# SMD.net
KiCad netlist of a schematic drawn in EAGLE
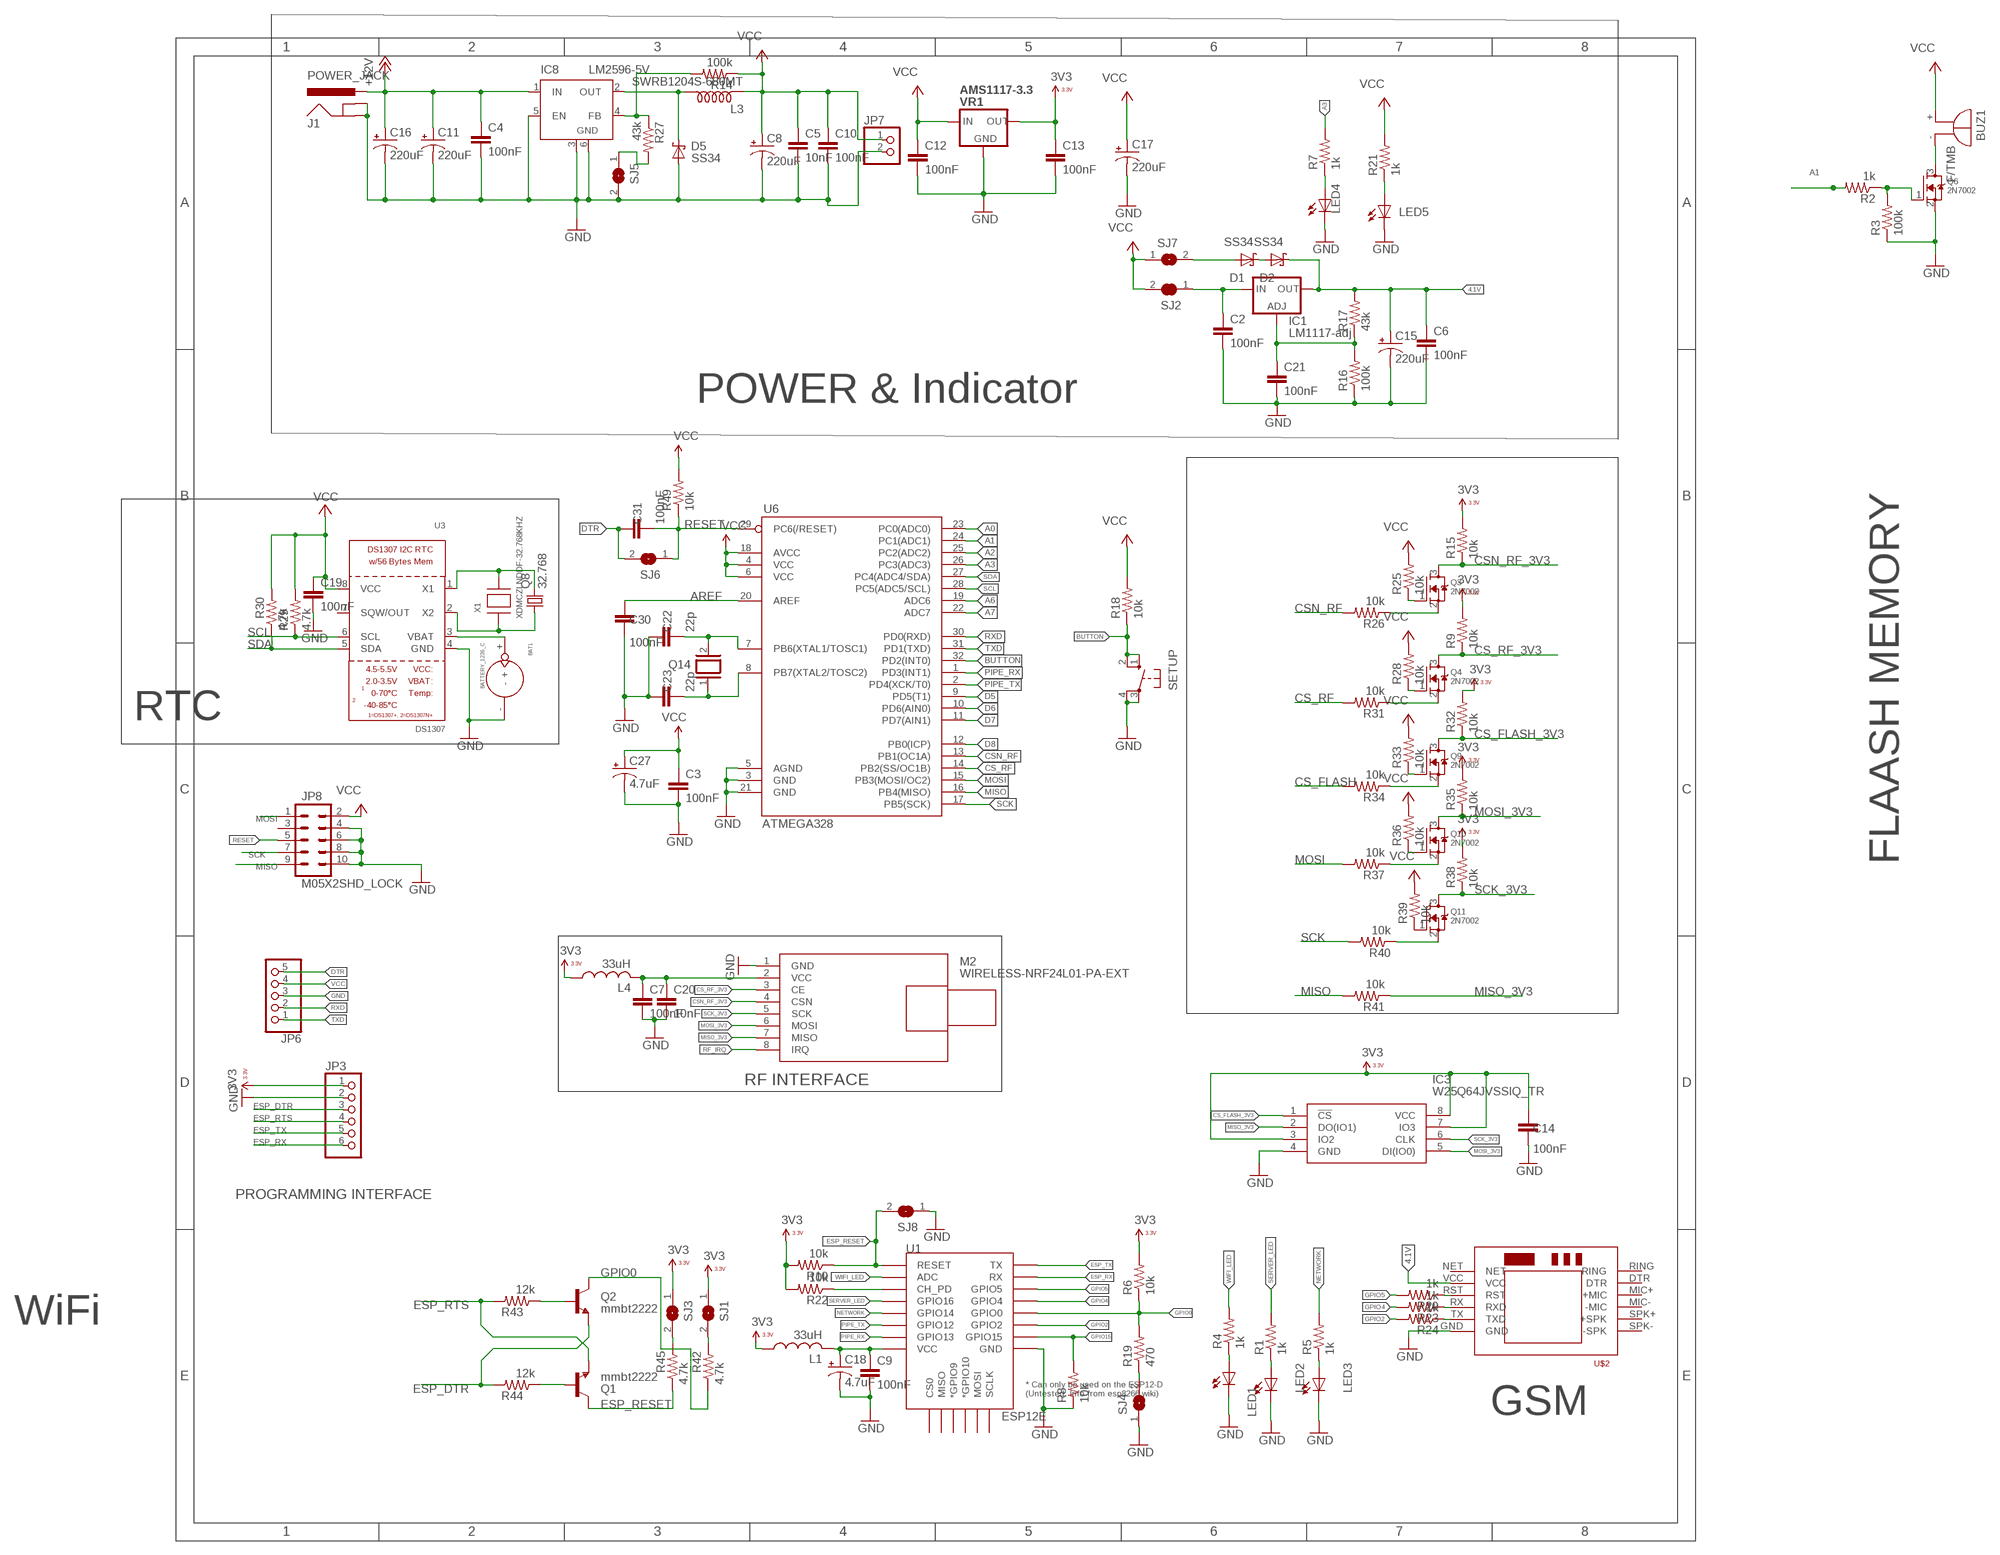
[diagram p0: schematic, sheet 1]

(export (version "E")
  (design (tool "Eeschema 10.0.6"))
  (components
    (comp (ref "BAT1")
      (value "BATTERY_1236_C")
      (footprint "eagle-import:BATTERY_1236_C")
      (libsource (lib "eagle-import") (part "BATTERY_1236_C"))
    )
    (comp (ref "BUZ1")
      (value "F/TMB")
      (footprint "eagle-import:F_TMB")
      (libsource (lib "eagle-import") (part "F/TMB"))
    )
    (comp (ref "C2")
      (value "100nF")
      (footprint "eagle-import:C0805")
      (libsource (lib "eagle-import") (part "C-EUC0805"))
    )
    (comp (ref "C3")
      (value "100nF")
      (footprint "eagle-import:C0805")
      (libsource (lib "eagle-import") (part "C-EUC0805"))
    )
    (comp (ref "C4")
      (value "100nF")
      (footprint "eagle-import:C0805")
      (libsource (lib "eagle-import") (part "C-EUC0805"))
    )
    (comp (ref "C5")
      (value "10nF")
      (footprint "eagle-import:C0805")
      (libsource (lib "eagle-import") (part "C-EUC0805"))
    )
    (comp (ref "C6")
      (value "100nF")
      (footprint "eagle-import:C0805")
      (libsource (lib "eagle-import") (part "C-EUC0805"))
    )
    (comp (ref "C7")
      (value "100nF")
      (footprint "eagle-import:C0805")
      (libsource (lib "eagle-import") (part "C-EUC0805"))
    )
    (comp (ref "C8")
      (value "220uF")
      (footprint "eagle-import:UD-6,3X7,7_NICHICON")
      (libsource (lib "eagle-import") (part "CPOL-USUD-6,3X7,7"))
    )
    (comp (ref "C9")
      (value "100nF")
      (footprint "eagle-import:C0805")
      (libsource (lib "eagle-import") (part "C-EUC0805"))
    )
    (comp (ref "C10")
      (value "100nF")
      (footprint "eagle-import:C0805")
      (libsource (lib "eagle-import") (part "C-EUC0805"))
    )
    (comp (ref "C11")
      (value "220uF")
      (footprint "eagle-import:UD-6,3X7,7_NICHICON")
      (libsource (lib "eagle-import") (part "CPOL-USUD-6,3X7,7"))
    )
    (comp (ref "C12")
      (value "100nF")
      (footprint "eagle-import:C0805")
      (libsource (lib "eagle-import") (part "C-EUC0805"))
    )
    (comp (ref "C13")
      (value "100nF")
      (footprint "eagle-import:C0805")
      (libsource (lib "eagle-import") (part "C-EUC0805"))
    )
    (comp (ref "C14")
      (value "100nF")
      (footprint "eagle-import:C0805")
      (libsource (lib "eagle-import") (part "C-EUC0805"))
    )
    (comp (ref "C15")
      (value "220uF")
      (footprint "eagle-import:UD-6,3X7,7_NICHICON")
      (libsource (lib "eagle-import") (part "CPOL-USUD-6,3X7,7"))
    )
    (comp (ref "C16")
      (value "220uF")
      (footprint "eagle-import:UD-6,3X7,7_NICHICON")
      (libsource (lib "eagle-import") (part "CPOL-USUD-6,3X7,7"))
    )
    (comp (ref "C17")
      (value "220uF")
      (footprint "eagle-import:UD-6,3X7,7_NICHICON")
      (libsource (lib "eagle-import") (part "CPOL-USUD-6,3X7,7"))
    )
    (comp (ref "C18")
      (value "4.7uF")
      (footprint "eagle-import:1206-POLAR")
      (libsource (lib "eagle-import") (part "100UF-POLAR-1206-6.3V-20%(TANT)"))
    )
    (comp (ref "C19")
      (value "100nF")
      (footprint "eagle-import:C0805")
      (libsource (lib "eagle-import") (part "C-EUC0805"))
    )
    (comp (ref "C20")
      (value "10nF")
      (footprint "eagle-import:C0805")
      (libsource (lib "eagle-import") (part "C-EUC0805"))
    )
    (comp (ref "C21")
      (value "100nF")
      (footprint "eagle-import:C0805")
      (libsource (lib "eagle-import") (part "C-EUC0805"))
    )
    (comp (ref "C22")
      (value "22p")
      (footprint "eagle-import:C0805")
      (libsource (lib "eagle-import") (part "C-EUC0805"))
    )
    (comp (ref "C23")
      (value "22p")
      (footprint "eagle-import:C0805")
      (libsource (lib "eagle-import") (part "C-EUC0805"))
    )
    (comp (ref "C27")
      (value "4.7uF")
      (footprint "eagle-import:1206-POLAR")
      (libsource (lib "eagle-import") (part "100UF-POLAR-1206-6.3V-20%(TANT)"))
    )
    (comp (ref "C30")
      (value "100nF")
      (footprint "eagle-import:C0805")
      (libsource (lib "eagle-import") (part "C-EUC0805"))
    )
    (comp (ref "C31")
      (value "100nF")
      (footprint "eagle-import:C0805")
      (libsource (lib "eagle-import") (part "C-EUC0805"))
    )
    (comp (ref "D1")
      (value "SS34")
      (footprint "eagle-import:SMB")
      (libsource (lib "eagle-import") (part "SCHOTTKY-DIODESMD"))
    )
    (comp (ref "D2")
      (value "SS34")
      (footprint "eagle-import:SMB")
      (libsource (lib "eagle-import") (part "SCHOTTKY-DIODESMD"))
    )
    (comp (ref "D5")
      (value "SS34")
      (footprint "eagle-import:SMB")
      (libsource (lib "eagle-import") (part "SCHOTTKY-DIODESMD"))
    )
    (comp (ref "IC1")
      (value "LM1117-adj")
      (footprint "eagle-import:SOT223")
      (libsource (lib "eagle-import") (part "LD117A?S25TR"))
    )
    (comp (ref "IC3")
      (value "W25Q64JVSSIQ_TR")
      (footprint "eagle-import:SOIC127P790X216-8N")
      (fields
        (field (name "MANUFACTURER_PART_NUMBER") "W25Q64JVSSIQ TR")
        (field (name "MOUSER_PART_NUMBER") "454-W25Q64JVSSIQTR")
      )
      (libsource (lib "eagle-import") (part "W25Q64JVSSIQ_TR"))
    )
    (comp (ref "IC8")
      (value "LM2596-5V")
      (footprint "eagle-import:TO263-5")
      (libsource (lib "eagle-import") (part "LM2596S"))
    )
    (comp (ref "J1")
      (value "POWER_JACK")
      (footprint "eagle-import:POWER_JACK_PTH")
      (libsource (lib "eagle-import") (part "POWER_JACK"))
    )
    (comp (ref "JP3")
      (value "PINHD-1X6")
      (footprint "eagle-import:1X06")
      (libsource (lib "eagle-import") (part "PINHD-1X6"))
    )
    (comp (ref "JP6")
      (value "PINHD-1X5")
      (footprint "eagle-import:1X05")
      (libsource (lib "eagle-import") (part "PINHD-1X5"))
    )
    (comp (ref "JP7")
      (value "PINHD-1X2")
      (footprint "eagle-import:1X02")
      (libsource (lib "eagle-import") (part "PINHD-1X2"))
    )
    (comp (ref "JP8")
      (value "M05X2SHD_LOCK")
      (footprint "eagle-import:2X5-SHROUDED_LOCK")
      (libsource (lib "eagle-import") (part "M05X2SHD_LOCK"))
    )
    (comp (ref "L1")
      (value "33uH")
      (footprint "eagle-import:L0805")
      (libsource (lib "eagle-import") (part "L-USL0805"))
    )
    (comp (ref "L3")
      (value "SWRB1204S-680MT")
      (footprint "eagle-import:D10F")
      (libsource (lib "eagle-import") (part "A814AY-330M"))
    )
    (comp (ref "L4")
      (value "33uH")
      (footprint "eagle-import:L0805")
      (libsource (lib "eagle-import") (part "L-USL0805"))
    )
    (comp (ref "LED1")
      (value "LED3MM")
      (footprint "eagle-import:LED3MM")
      (libsource (lib "eagle-import") (part "LED3MM"))
    )
    (comp (ref "LED2")
      (value "LED3MM")
      (footprint "eagle-import:LED3MM")
      (libsource (lib "eagle-import") (part "LED3MM"))
    )
    (comp (ref "LED3")
      (value "LED3MM")
      (footprint "eagle-import:LED3MM")
      (libsource (lib "eagle-import") (part "LED3MM"))
    )
    (comp (ref "LED4")
      (value "LED3MM")
      (footprint "eagle-import:LED3MM")
      (libsource (lib "eagle-import") (part "LED3MM"))
    )
    (comp (ref "LED5")
      (value "LED3MM")
      (footprint "eagle-import:LED3MM")
      (libsource (lib "eagle-import") (part "LED3MM"))
    )
    (comp (ref "M2")
      (value "WIRELESS-NRF24L01-PA-EXT")
      (footprint "eagle-import:WIRELESS-NRF24L01-PA-EXT")
      (libsource (lib "eagle-import") (part "WIRELESS-NRF24L01-PA-EXT"))
    )
    (comp (ref "Q1")
      (value "mmbt2222")
      (footprint "eagle-import:SOT23-3")
      (libsource (lib "eagle-import") (part "TRANSISTOR_NPNSOT23-3"))
    )
    (comp (ref "Q2")
      (value "mmbt2222")
      (footprint "eagle-import:SOT23-3")
      (libsource (lib "eagle-import") (part "TRANSISTOR_NPNSOT23-3"))
    )
    (comp (ref "Q3")
      (value "2N7002")
      (footprint "eagle-import:SOT23")
      (libsource (lib "eagle-import") (part "MOSFET-NREFLOW"))
    )
    (comp (ref "Q4")
      (value "2N7002")
      (footprint "eagle-import:SOT23")
      (libsource (lib "eagle-import") (part "MOSFET-NREFLOW"))
    )
    (comp (ref "Q6")
      (value "2N7002")
      (footprint "eagle-import:SOT23")
      (libsource (lib "eagle-import") (part "MOSFET-NREFLOW"))
    )
    (comp (ref "Q8")
      (value "32.768")
      (footprint "eagle-import:TC26H")
      (libsource (lib "eagle-import") (part "CRYTALTC26H"))
    )
    (comp (ref "Q9")
      (value "2N7002")
      (footprint "eagle-import:SOT23")
      (libsource (lib "eagle-import") (part "MOSFET-NREFLOW"))
    )
    (comp (ref "Q10")
      (value "2N7002")
      (footprint "eagle-import:SOT23")
      (libsource (lib "eagle-import") (part "MOSFET-NREFLOW"))
    )
    (comp (ref "Q11")
      (value "2N7002")
      (footprint "eagle-import:SOT23")
      (libsource (lib "eagle-import") (part "MOSFET-NREFLOW"))
    )
    (comp (ref "Q14")
      (value "XTAL/S")
      (footprint "eagle-import:QS")
      (libsource (lib "eagle-import") (part "XTAL/S"))
    )
    (comp (ref "R1")
      (value "1k")
      (footprint "eagle-import:R0805")
      (libsource (lib "eagle-import") (part "resistor_R-US_R0805"))
    )
    (comp (ref "R2")
      (value "1k")
      (footprint "eagle-import:R0805")
      (libsource (lib "eagle-import") (part "resistor_R-US_R0805"))
    )
    (comp (ref "R3")
      (value "100k")
      (footprint "eagle-import:R0805")
      (libsource (lib "eagle-import") (part "resistor_R-US_R0805"))
    )
    (comp (ref "R4")
      (value "1k")
      (footprint "eagle-import:R0805")
      (libsource (lib "eagle-import") (part "resistor_R-US_R0805"))
    )
    (comp (ref "R5")
      (value "1k")
      (footprint "eagle-import:R0805")
      (libsource (lib "eagle-import") (part "resistor_R-US_R0805"))
    )
    (comp (ref "R6")
      (value "10k")
      (footprint "eagle-import:R0805")
      (libsource (lib "eagle-import") (part "resistor_R-US_R0805"))
    )
    (comp (ref "R7")
      (value "1k")
      (footprint "eagle-import:R0805")
      (libsource (lib "eagle-import") (part "resistor_R-US_R0805"))
    )
    (comp (ref "R8")
      (value "10k")
      (footprint "eagle-import:R0805")
      (libsource (lib "eagle-import") (part "resistor_R-US_R0805"))
    )
    (comp (ref "R9")
      (value "10k")
      (footprint "eagle-import:R0805")
      (libsource (lib "eagle-import") (part "resistor_R-US_R0805"))
    )
    (comp (ref "R10")
      (value "10k")
      (footprint "eagle-import:R0805")
      (libsource (lib "eagle-import") (part "resistor_R-US_R0805"))
    )
    (comp (ref "R14")
      (value "100k")
      (footprint "eagle-import:R0805")
      (libsource (lib "eagle-import") (part "resistor_R-US_R0805"))
    )
    (comp (ref "R15")
      (value "10k")
      (footprint "eagle-import:R0805")
      (libsource (lib "eagle-import") (part "resistor_R-US_R0805"))
    )
    (comp (ref "R16")
      (value "100k")
      (footprint "eagle-import:R0805")
      (libsource (lib "eagle-import") (part "resistor_R-US_R0805"))
    )
    (comp (ref "R17")
      (value "43k")
      (footprint "eagle-import:R0805")
      (libsource (lib "eagle-import") (part "resistor_R-US_R0805"))
    )
    (comp (ref "R18")
      (value "10k")
      (footprint "eagle-import:R0805")
      (libsource (lib "eagle-import") (part "resistor_R-US_R0805"))
    )
    (comp (ref "R19")
      (value "470")
      (footprint "eagle-import:R0805")
      (libsource (lib "eagle-import") (part "resistor_R-US_R0805"))
    )
    (comp (ref "R20")
      (value "1k")
      (footprint "eagle-import:R0805")
      (libsource (lib "eagle-import") (part "resistor_R-US_R0805"))
    )
    (comp (ref "R21")
      (value "1k")
      (footprint "eagle-import:R0805")
      (libsource (lib "eagle-import") (part "resistor_R-US_R0805"))
    )
    (comp (ref "R22")
      (value "10k")
      (footprint "eagle-import:R0805")
      (libsource (lib "eagle-import") (part "resistor_R-US_R0805"))
    )
    (comp (ref "R23")
      (value "1k")
      (footprint "eagle-import:R0805")
      (libsource (lib "eagle-import") (part "resistor_R-US_R0805"))
    )
    (comp (ref "R24")
      (value "1k")
      (footprint "eagle-import:R0805")
      (libsource (lib "eagle-import") (part "resistor_R-US_R0805"))
    )
    (comp (ref "R25")
      (value "10k")
      (footprint "eagle-import:R0805")
      (libsource (lib "eagle-import") (part "resistor_R-US_R0805"))
    )
    (comp (ref "R26")
      (value "10k")
      (footprint "eagle-import:R0805")
      (libsource (lib "eagle-import") (part "resistor_R-US_R0805"))
    )
    (comp (ref "R27")
      (value "43k")
      (footprint "eagle-import:R0805")
      (libsource (lib "eagle-import") (part "resistor_R-US_R0805"))
    )
    (comp (ref "R28")
      (value "10k")
      (footprint "eagle-import:R0805")
      (libsource (lib "eagle-import") (part "resistor_R-US_R0805"))
    )
    (comp (ref "R29")
      (value "4.7k")
      (footprint "eagle-import:R0805")
      (libsource (lib "eagle-import") (part "resistor_R-US_R0805"))
    )
    (comp (ref "R30")
      (value "4.7k")
      (footprint "eagle-import:R0805")
      (libsource (lib "eagle-import") (part "resistor_R-US_R0805"))
    )
    (comp (ref "R31")
      (value "10k")
      (footprint "eagle-import:R0805")
      (libsource (lib "eagle-import") (part "resistor_R-US_R0805"))
    )
    (comp (ref "R32")
      (value "10k")
      (footprint "eagle-import:R0805")
      (libsource (lib "eagle-import") (part "resistor_R-US_R0805"))
    )
    (comp (ref "R33")
      (value "10k")
      (footprint "eagle-import:R0805")
      (libsource (lib "eagle-import") (part "resistor_R-US_R0805"))
    )
    (comp (ref "R34")
      (value "10k")
      (footprint "eagle-import:R0805")
      (libsource (lib "eagle-import") (part "resistor_R-US_R0805"))
    )
    (comp (ref "R35")
      (value "10k")
      (footprint "eagle-import:R0805")
      (libsource (lib "eagle-import") (part "resistor_R-US_R0805"))
    )
    (comp (ref "R36")
      (value "10k")
      (footprint "eagle-import:R0805")
      (libsource (lib "eagle-import") (part "resistor_R-US_R0805"))
    )
    (comp (ref "R37")
      (value "10k")
      (footprint "eagle-import:R0805")
      (libsource (lib "eagle-import") (part "resistor_R-US_R0805"))
    )
    (comp (ref "R38")
      (value "10k")
      (footprint "eagle-import:R0805")
      (libsource (lib "eagle-import") (part "resistor_R-US_R0805"))
    )
    (comp (ref "R39")
      (value "10k")
      (footprint "eagle-import:R0805")
      (libsource (lib "eagle-import") (part "resistor_R-US_R0805"))
    )
    (comp (ref "R40")
      (value "10k")
      (footprint "eagle-import:R0805")
      (libsource (lib "eagle-import") (part "resistor_R-US_R0805"))
    )
    (comp (ref "R41")
      (value "10k")
      (footprint "eagle-import:R0805")
      (libsource (lib "eagle-import") (part "resistor_R-US_R0805"))
    )
    (comp (ref "R42")
      (value "4.7k")
      (footprint "eagle-import:R0805")
      (libsource (lib "eagle-import") (part "resistor_R-US_R0805"))
    )
    (comp (ref "R43")
      (value "12k")
      (footprint "eagle-import:R0805")
      (libsource (lib "eagle-import") (part "resistor_R-US_R0805"))
    )
    (comp (ref "R44")
      (value "12k")
      (footprint "eagle-import:R0805")
      (libsource (lib "eagle-import") (part "resistor_R-US_R0805"))
    )
    (comp (ref "R45")
      (value "4.7k")
      (footprint "eagle-import:R0805")
      (libsource (lib "eagle-import") (part "resistor_R-US_R0805"))
    )
    (comp (ref "R49")
      (value "10k")
      (footprint "eagle-import:R0805")
      (libsource (lib "eagle-import") (part "R-US_R0805"))
    )
    (comp (ref "SETUP")
      (value "10-XX")
      (footprint "eagle-import:B3F-10XX")
      (fields (field (name "MPN") "B3F-1000"))
      (libsource (lib "eagle-import") (part "10-XX"))
    )
    (comp (ref "SJ1") (value "SJ") (footprint "eagle-import:SJ") (libsource (lib "eagle-import") (part "SJ")))
    (comp (ref "SJ2")
      (value "SOLDERJUMPER_CLOSED")
      (footprint "eagle-import:SOLDERJUMPER_CLOSEDWIRE")
      (libsource (lib "eagle-import") (part "SOLDERJUMPER_CLOSED"))
    )
    (comp (ref "SJ3") (value "SJ") (footprint "eagle-import:SJ") (libsource (lib "eagle-import") (part "SJ")))
    (comp (ref "SJ4") (value "SJ") (footprint "eagle-import:SJ") (libsource (lib "eagle-import") (part "SJ")))
    (comp (ref "SJ5") (value "SJ") (footprint "eagle-import:SJ") (libsource (lib "eagle-import") (part "SJ")))
    (comp (ref "SJ6") (value "SJ") (footprint "eagle-import:SJ") (libsource (lib "eagle-import") (part "SJ")))
    (comp (ref "SJ7") (value "SJ") (footprint "eagle-import:SJ") (libsource (lib "eagle-import") (part "SJ")))
    (comp (ref "SJ8") (value "SJ") (footprint "eagle-import:SJ") (libsource (lib "eagle-import") (part "SJ")))
    (comp (ref "U$2")
      (value "SIM800LMODULE")
      (footprint "eagle-import:SIM800LMODULE")
      (libsource (lib "eagle-import") (part "SIM800LMODULE"))
    )
    (comp (ref "U1")
      (value "ESP12E")
      (footprint "eagle-import:ESP12E-SMD")
      (libsource (lib "eagle-import") (part "ESP12ESMD"))
    )
    (comp (ref "U3")
      (value "DS1307")
      (footprint "eagle-import:SOIC8_150MIL")
      (libsource (lib "eagle-import") (part "RTC_DS1307"))
    )
    (comp (ref "U6")
      (value "ATMEGA328")
      (footprint "eagle-import:TQFP32-08")
      (libsource (lib "eagle-import") (part "ATMEGA168"))
    )
    (comp (ref "VR1")
      (value "AMS1117-3.3")
      (footprint "eagle-import:SOT223")
      (libsource (lib "eagle-import") (part "NCP1117ST50T3G"))
    )
    (comp (ref "X1")
      (value "XDMCZLNDDF-32.768KHZ")
      (footprint "eagle-import:XTAL3215")
      (libsource (lib "eagle-import") (part "XTAL-3.2X1.5"))
    )
  )
  (nets
    (net (code "1") (name "+12V") (class "Default")
      (node (ref "C11") (pin "+") (pinfunction "+_+") (pintype "passive"))
      (node (ref "C16") (pin "+") (pinfunction "+_+") (pintype "passive"))
      (node (ref "C4") (pin "1") (pinfunction "1_1") (pintype "passive"))
      (node (ref "IC8") (pin "1") (pinfunction "IN_1") (pintype "input"))
      (node (ref "J1") (pin "PWR") (pinfunction "PWR_PWR") (pintype "bidirectional"))
    )
    (net (code "2") (name "/AREF") (class "Default")
      (node (ref "C30") (pin "2") (pinfunction "2_2") (pintype "passive"))
      (node (ref "U6") (pin "20") (pinfunction "AREF_20") (pintype "bidirectional"))
    )
    (net (code "3") (name "/CS_FLASH") (class "Default")
      (node (ref "R34") (pin "2") (pinfunction "2_2") (pintype "passive"))
    )
    (net (code "4") (name "/ESP_DTR") (class "Default")
      (node (ref "JP3") (pin "3") (pinfunction "3_3") (pintype "passive"))
      (node (ref "Q2") (pin "2") (pinfunction "E_2") (pintype "passive"))
      (node (ref "R44") (pin "2") (pinfunction "2_2") (pintype "passive"))
    )
    (net (code "5") (name "/ESP_RTS") (class "Default")
      (node (ref "JP3") (pin "4") (pinfunction "4_4") (pintype "passive"))
      (node (ref "Q1") (pin "2") (pinfunction "E_2") (pintype "passive"))
      (node (ref "R43") (pin "2") (pinfunction "2_2") (pintype "passive"))
    )
    (net (code "6") (name "3V3") (class "Default")
      (node (ref "C13") (pin "1") (pinfunction "1_1") (pintype "passive"))
      (node (ref "C14") (pin "2") (pinfunction "2_2") (pintype "passive"))
      (node (ref "IC3") (pin "3") (pinfunction "IO2_3") (pintype "bidirectional"))
      (node (ref "IC3") (pin "7") (pinfunction "IO3_7") (pintype "bidirectional"))
      (node (ref "IC3") (pin "8") (pinfunction "VCC_8") (pintype "bidirectional"))
      (node (ref "JP3") (pin "1") (pinfunction "1_1") (pintype "passive"))
      (node (ref "L1") (pin "1") (pinfunction "1_1") (pintype "passive"))
      (node (ref "L4") (pin "1") (pinfunction "1_1") (pintype "passive"))
      (node (ref "R10") (pin "2") (pinfunction "2_2") (pintype "passive"))
      (node (ref "R15") (pin "2") (pinfunction "2_2") (pintype "passive"))
      (node (ref "R22") (pin "2") (pinfunction "2_2") (pintype "passive"))
      (node (ref "R32") (pin "2") (pinfunction "2_2") (pintype "passive"))
      (node (ref "R35") (pin "2") (pinfunction "2_2") (pintype "passive"))
      (node (ref "R38") (pin "2") (pinfunction "2_2") (pintype "passive"))
      (node (ref "R6") (pin "2") (pinfunction "2_2") (pintype "passive"))
      (node (ref "R9") (pin "2") (pinfunction "2_2") (pintype "passive"))
      (node (ref "SJ1") (pin "1") (pinfunction "1_1") (pintype "passive"))
      (node (ref "SJ3") (pin "1") (pinfunction "1_1") (pintype "passive"))
      (node (ref "VR1") (pin "2") (pinfunction "OUT_2") (pintype "output"))
      (node (ref "VR1") (pin "4") (pinfunction "OUT_4") (pintype "output"))
    )
    (net (code "7") (name "4.1V") (class "Default")
      (node (ref "C15") (pin "+") (pinfunction "+_+") (pintype "passive"))
      (node (ref "C6") (pin "1") (pinfunction "1_1") (pintype "passive"))
      (node (ref "D2") (pin "C") (pinfunction "C_C") (pintype "passive"))
      (node (ref "IC1") (pin "4") (pinfunction "OUT_4") (pintype "passive"))
      (node (ref "R17") (pin "2") (pinfunction "2_2") (pintype "passive"))
      (node (ref "U$2") (pin "VCC") (pinfunction "VCC_VCC") (pintype "bidirectional"))
    )
    (net (code "8") (name "A0") (class "Default")
      (node (ref "U6") (pin "23") (pinfunction "PC0(ADC0)_23") (pintype "bidirectional"))
    )
    (net (code "9") (name "A1") (class "Default")
      (node (ref "R2") (pin "2") (pinfunction "2_2") (pintype "passive"))
      (node (ref "U6") (pin "24") (pinfunction "PC1(ADC1)_24") (pintype "bidirectional"))
    )
    (net (code "10") (name "A2") (class "Default")
      (node (ref "U6") (pin "25") (pinfunction "PC2(ADC2)_25") (pintype "bidirectional"))
    )
    (net (code "11") (name "A3") (class "Default")
      (node (ref "R7") (pin "2") (pinfunction "2_2") (pintype "passive"))
      (node (ref "U6") (pin "26") (pinfunction "PC3(ADC3)_26") (pintype "bidirectional"))
    )
    (net (code "12") (name "A6") (class "Default")
      (node (ref "U6") (pin "19") (pinfunction "ADC6_19") (pintype "bidirectional"))
    )
    (net (code "13") (name "A7") (class "Default")
      (node (ref "U6") (pin "22") (pinfunction "ADC7_22") (pintype "bidirectional"))
    )
    (net (code "14") (name "BUTTON") (class "Default")
      (node (ref "R18") (pin "1") (pinfunction "1_1") (pintype "passive"))
      (node (ref "SETUP") (pin "1") (pinfunction "S_1") (pintype "passive"))
      (node (ref "SETUP") (pin "2") (pinfunction "S1_2") (pintype "passive"))
      (node (ref "U6") (pin "32") (pinfunction "PD2(INT0)_32") (pintype "bidirectional"))
    )
    (net (code "15") (name "CSN_RF") (class "Default")
      (node (ref "R26") (pin "2") (pinfunction "2_2") (pintype "passive"))
      (node (ref "U6") (pin "13") (pinfunction "PB1(OC1A)_13") (pintype "bidirectional"))
    )
    (net (code "16") (name "CSN_RF_3V3") (class "Default")
      (node (ref "M2") (pin "4") (pinfunction "CSN_4") (pintype "bidirectional"))
      (node (ref "Q3") (pin "3") (pinfunction "D_3") (pintype "bidirectional"))
      (node (ref "R15") (pin "1") (pinfunction "1_1") (pintype "passive"))
    )
    (net (code "17") (name "CS_FLASH_3V3") (class "Default")
      (node (ref "IC3") (pin "1") (pinfunction "~{CS}_1") (pintype "bidirectional"))
      (node (ref "Q9") (pin "3") (pinfunction "D_3") (pintype "bidirectional"))
      (node (ref "R32") (pin "1") (pinfunction "1_1") (pintype "passive"))
    )
    (net (code "18") (name "CS_RF") (class "Default")
      (node (ref "R31") (pin "2") (pinfunction "2_2") (pintype "passive"))
      (node (ref "U6") (pin "14") (pinfunction "PB2(SS/OC1B)_14") (pintype "bidirectional"))
    )
    (net (code "19") (name "CS_RF_3V3") (class "Default")
      (node (ref "M2") (pin "3") (pinfunction "CE_3") (pintype "bidirectional"))
      (node (ref "Q4") (pin "3") (pinfunction "D_3") (pintype "bidirectional"))
      (node (ref "R9") (pin "1") (pinfunction "1_1") (pintype "passive"))
    )
    (net (code "20") (name "D5") (class "Default")
      (node (ref "U6") (pin "9") (pinfunction "PD5(T1)_9") (pintype "bidirectional"))
    )
    (net (code "21") (name "D6") (class "Default")
      (node (ref "U6") (pin "10") (pinfunction "PD6(AIN0)_10") (pintype "bidirectional"))
    )
    (net (code "22") (name "D7") (class "Default")
      (node (ref "U6") (pin "11") (pinfunction "PD7(AIN1)_11") (pintype "bidirectional"))
    )
    (net (code "23") (name "D8") (class "Default")
      (node (ref "U6") (pin "12") (pinfunction "PB0(ICP)_12") (pintype "bidirectional"))
    )
    (net (code "24") (name "DTR") (class "Default")
      (node (ref "C31") (pin "2") (pinfunction "2_2") (pintype "passive"))
      (node (ref "JP6") (pin "5") (pinfunction "5_5") (pintype "passive"))
      (node (ref "SJ6") (pin "2") (pinfunction "2_2") (pintype "passive"))
    )
    (net (code "25") (name "ESP_RESET") (class "Default")
      (node (ref "Q1") (pin "3") (pinfunction "C_3") (pintype "passive"))
      (node (ref "R10") (pin "1") (pinfunction "1_1") (pintype "passive"))
      (node (ref "R45") (pin "1") (pinfunction "1_1") (pintype "passive"))
      (node (ref "SJ8") (pin "2") (pinfunction "2_2") (pintype "passive"))
      (node (ref "U1") (pin "RESET") (pinfunction "RESET_RESET") (pintype "bidirectional"))
    )
    (net (code "26") (name "ESP_RX") (class "Default")
      (node (ref "JP3") (pin "6") (pinfunction "6_6") (pintype "passive"))
      (node (ref "U1") (pin "RXD0") (pinfunction "RX_RXD0") (pintype "bidirectional"))
    )
    (net (code "27") (name "ESP_TX") (class "Default")
      (node (ref "JP3") (pin "5") (pinfunction "5_5") (pintype "passive"))
      (node (ref "U1") (pin "TXD0") (pinfunction "TX_TXD0") (pintype "bidirectional"))
    )
    (net (code "28") (name "GND") (class "Default")
      (node (ref "BAT1") (pin "-") (pinfunction "-_-") (pintype "bidirectional"))
      (node (ref "C10") (pin "2") (pinfunction "2_2") (pintype "passive"))
      (node (ref "C11") (pin "-") (pinfunction "-_-") (pintype "passive"))
      (node (ref "C12") (pin "2") (pinfunction "2_2") (pintype "passive"))
      (node (ref "C13") (pin "2") (pinfunction "2_2") (pintype "passive"))
      (node (ref "C14") (pin "1") (pinfunction "1_1") (pintype "passive"))
      (node (ref "C15") (pin "-") (pinfunction "-_-") (pintype "passive"))
      (node (ref "C16") (pin "-") (pinfunction "-_-") (pintype "passive"))
      (node (ref "C17") (pin "-") (pinfunction "-_-") (pintype "passive"))
      (node (ref "C18") (pin "2") (pinfunction "-_2") (pintype "passive"))
      (node (ref "C19") (pin "2") (pinfunction "2_2") (pintype "passive"))
      (node (ref "C2") (pin "2") (pinfunction "2_2") (pintype "passive"))
      (node (ref "C20") (pin "2") (pinfunction "2_2") (pintype "passive"))
      (node (ref "C21") (pin "2") (pinfunction "2_2") (pintype "passive"))
      (node (ref "C22") (pin "2") (pinfunction "2_2") (pintype "passive"))
      (node (ref "C23") (pin "2") (pinfunction "2_2") (pintype "passive"))
      (node (ref "C27") (pin "2") (pinfunction "-_2") (pintype "passive"))
      (node (ref "C3") (pin "2") (pinfunction "2_2") (pintype "passive"))
      (node (ref "C30") (pin "1") (pinfunction "1_1") (pintype "passive"))
      (node (ref "C4") (pin "2") (pinfunction "2_2") (pintype "passive"))
      (node (ref "C5") (pin "2") (pinfunction "2_2") (pintype "passive"))
      (node (ref "C6") (pin "2") (pinfunction "2_2") (pintype "passive"))
      (node (ref "C7") (pin "2") (pinfunction "2_2") (pintype "passive"))
      (node (ref "C8") (pin "-") (pinfunction "-_-") (pintype "passive"))
      (node (ref "C9") (pin "2") (pinfunction "2_2") (pintype "passive"))
      (node (ref "D5") (pin "A") (pinfunction "A_A") (pintype "passive"))
      (node (ref "IC3") (pin "4") (pinfunction "GND_4") (pintype "bidirectional"))
      (node (ref "IC8") (pin "3") (pinfunction "GND_3") (pintype "power_in"))
      (node (ref "IC8") (pin "5") (pinfunction "EN_5") (pintype "input"))
      (node (ref "IC8") (pin "6") (pinfunction "GND_6") (pintype "power_in"))
      (node (ref "J1") (pin "GND") (pinfunction "GND_GND") (pintype "bidirectional"))
      (node (ref "J1") (pin "GNDBREAK") (pinfunction "GNDBREAK_GNDBREAK") (pintype "bidirectional"))
      (node (ref "JP3") (pin "2") (pinfunction "2_2") (pintype "passive"))
      (node (ref "JP6") (pin "3") (pinfunction "3_3") (pintype "passive"))
      (node (ref "JP7") (pin "2") (pinfunction "2_2") (pintype "passive"))
      (node (ref "JP8") (pin "10") (pinfunction "10_10") (pintype "passive"))
      (node (ref "JP8") (pin "4") (pinfunction "4_4") (pintype "passive"))
      (node (ref "JP8") (pin "6") (pinfunction "6_6") (pintype "passive"))
      (node (ref "JP8") (pin "8") (pinfunction "8_8") (pintype "passive"))
      (node (ref "LED1") (pin "K") (pinfunction "C_K") (pintype "passive"))
      (node (ref "LED2") (pin "K") (pinfunction "C_K") (pintype "passive"))
      (node (ref "LED3") (pin "K") (pinfunction "C_K") (pintype "passive"))
      (node (ref "LED4") (pin "K") (pinfunction "C_K") (pintype "passive"))
      (node (ref "LED5") (pin "K") (pinfunction "C_K") (pintype "passive"))
      (node (ref "M2") (pin "1") (pinfunction "GND_1") (pintype "power_in"))
      (node (ref "Q6") (pin "2") (pinfunction "S_2") (pintype "bidirectional"))
      (node (ref "R16") (pin "1") (pinfunction "1_1") (pintype "passive"))
      (node (ref "R3") (pin "1") (pinfunction "1_1") (pintype "passive"))
      (node (ref "R8") (pin "1") (pinfunction "1_1") (pintype "passive"))
      (node (ref "SETUP") (pin "3") (pinfunction "P_3") (pintype "passive"))
      (node (ref "SETUP") (pin "4") (pinfunction "P1_4") (pintype "passive"))
      (node (ref "SJ4") (pin "1") (pinfunction "1_1") (pintype "passive"))
      (node (ref "SJ5") (pin "2") (pinfunction "2_2") (pintype "passive"))
      (node (ref "SJ8") (pin "1") (pinfunction "1_1") (pintype "passive"))
      (node (ref "U$2") (pin "GND") (pinfunction "GND_GND") (pintype "bidirectional"))
      (node (ref "U1") (pin "GND") (pinfunction "GND_GND") (pintype "bidirectional"))
      (node (ref "U3") (pin "4") (pinfunction "GND_4") (pintype "bidirectional"))
      (node (ref "U6") (pin "21") (pinfunction "GND_21") (pintype "bidirectional"))
      (node (ref "U6") (pin "3") (pinfunction "GND_3") (pintype "bidirectional"))
      (node (ref "U6") (pin "5") (pinfunction "AGND_5") (pintype "bidirectional"))
      (node (ref "VR1") (pin "1") (pinfunction "GND_1") (pintype "input"))
    )
    (net (code "29") (name "GPIO0") (class "Default")
      (node (ref "Q2") (pin "3") (pinfunction "C_3") (pintype "passive"))
      (node (ref "R19") (pin "2") (pinfunction "2_2") (pintype "passive"))
      (node (ref "R42") (pin "1") (pinfunction "1_1") (pintype "passive"))
      (node (ref "R6") (pin "1") (pinfunction "1_1") (pintype "passive"))
      (node (ref "U1") (pin "GPIO0") (pinfunction "GPIO0_GPIO0") (pintype "bidirectional"))
    )
    (net (code "30") (name "GPIO2") (class "Default")
      (node (ref "R24") (pin "2") (pinfunction "2_2") (pintype "passive"))
      (node (ref "U1") (pin "GPIO2") (pinfunction "GPIO2_GPIO2") (pintype "bidirectional"))
    )
    (net (code "31") (name "GPIO4") (class "Default")
      (node (ref "R23") (pin "2") (pinfunction "2_2") (pintype "passive"))
      (node (ref "U1") (pin "GPIO4") (pinfunction "GPIO4_GPIO4") (pintype "bidirectional"))
    )
    (net (code "32") (name "GPIO5") (class "Default")
      (node (ref "R20") (pin "2") (pinfunction "2_2") (pintype "passive"))
      (node (ref "U1") (pin "GPIO5") (pinfunction "GPIO5_GPIO5") (pintype "bidirectional"))
    )
    (net (code "33") (name "GPIO15") (class "Default")
      (node (ref "R8") (pin "2") (pinfunction "2_2") (pintype "passive"))
      (node (ref "U1") (pin "GPIO15") (pinfunction "GPIO15_GPIO15") (pintype "bidirectional"))
    )
    (net (code "34") (name "MISO") (class "Default")
      (node (ref "JP8") (pin "9") (pinfunction "9_9") (pintype "passive"))
      (node (ref "R41") (pin "2") (pinfunction "2_2") (pintype "passive"))
      (node (ref "U6") (pin "16") (pinfunction "PB4(MISO)_16") (pintype "bidirectional"))
    )
    (net (code "35") (name "MISO_3V3") (class "Default")
      (node (ref "IC3") (pin "2") (pinfunction "DO(IO1)_2") (pintype "bidirectional"))
      (node (ref "M2") (pin "7") (pinfunction "MISO_7") (pintype "bidirectional"))
      (node (ref "R41") (pin "1") (pinfunction "1_1") (pintype "passive"))
    )
    (net (code "36") (name "MOSI") (class "Default")
      (node (ref "JP8") (pin "1") (pinfunction "1_1") (pintype "passive"))
      (node (ref "R37") (pin "2") (pinfunction "2_2") (pintype "passive"))
      (node (ref "U6") (pin "15") (pinfunction "PB3(MOSI/OC2)_15") (pintype "bidirectional"))
    )
    (net (code "37") (name "MOSI_3V3") (class "Default")
      (node (ref "IC3") (pin "5") (pinfunction "DI(IO0)_5") (pintype "bidirectional"))
      (node (ref "M2") (pin "6") (pinfunction "MOSI_6") (pintype "bidirectional"))
      (node (ref "Q10") (pin "3") (pinfunction "D_3") (pintype "bidirectional"))
      (node (ref "R35") (pin "1") (pinfunction "1_1") (pintype "passive"))
    )
    (net (code "38") (name "NETWORK") (class "Default")
      (node (ref "R5") (pin "2") (pinfunction "2_2") (pintype "passive"))
      (node (ref "U1") (pin "GPIO14") (pinfunction "GPIO14_GPIO14") (pintype "bidirectional"))
    )
    (net (code "39") (name "Net-(C18-+)") (class "Default")
      (node (ref "C18") (pin "1") (pinfunction "+_1") (pintype "passive"))
      (node (ref "C9") (pin "1") (pinfunction "1_1") (pintype "passive"))
      (node (ref "L1") (pin "2") (pinfunction "2_2") (pintype "passive"))
      (node (ref "U1") (pin "VCC") (pinfunction "VCC_VCC") (pintype "bidirectional"))
    )
    (net (code "40") (name "Net-(D1-PadA)") (class "Default")
      (node (ref "D1") (pin "A") (pinfunction "A_A") (pintype "passive"))
      (node (ref "SJ7") (pin "2") (pinfunction "2_2") (pintype "passive"))
    )
    (net (code "41") (name "Net-(D1-PadC)") (class "Default")
      (node (ref "D1") (pin "C") (pinfunction "C_C") (pintype "passive"))
      (node (ref "D2") (pin "A") (pinfunction "A_A") (pintype "passive"))
    )
    (net (code "42") (name "Net-(IC1-ADJ)") (class "Default")
      (node (ref "C21") (pin "1") (pinfunction "1_1") (pintype "passive"))
      (node (ref "IC1") (pin "1") (pinfunction "ADJ_1") (pintype "input"))
      (node (ref "R16") (pin "2") (pinfunction "2_2") (pintype "passive"))
      (node (ref "R17") (pin "1") (pinfunction "1_1") (pintype "passive"))
    )
    (net (code "43") (name "Net-(IC1-IN)") (class "Default")
      (node (ref "C2") (pin "1") (pinfunction "1_1") (pintype "passive"))
      (node (ref "IC1") (pin "3") (pinfunction "IN_3") (pintype "input"))
      (node (ref "SJ2") (pin "1") (pinfunction "1_1") (pintype "passive"))
    )
    (net (code "44") (name "Net-(IC8-FB)") (class "Default")
      (node (ref "IC8") (pin "4") (pinfunction "FB_4") (pintype "input"))
      (node (ref "R14") (pin "2") (pinfunction "2_2") (pintype "passive"))
      (node (ref "R27") (pin "1") (pinfunction "1_1") (pintype "passive"))
    )
    (net (code "45") (name "Net-(IC8-OUT)") (class "Default")
      (node (ref "D5") (pin "C") (pinfunction "C_C") (pintype "passive"))
      (node (ref "IC8") (pin "2") (pinfunction "OUT_2") (pintype "output"))
      (node (ref "L3") (pin "2") (pinfunction "2_2") (pintype "passive"))
    )
    (net (code "46") (name "Net-(LED1-PadA)") (class "Default")
      (node (ref "LED1") (pin "A") (pinfunction "A_A") (pintype "passive"))
      (node (ref "R4") (pin "1") (pinfunction "1_1") (pintype "passive"))
    )
    (net (code "47") (name "Net-(LED2-PadA)") (class "Default")
      (node (ref "LED2") (pin "A") (pinfunction "A_A") (pintype "passive"))
      (node (ref "R1") (pin "1") (pinfunction "1_1") (pintype "passive"))
    )
    (net (code "48") (name "Net-(LED3-PadA)") (class "Default")
      (node (ref "LED3") (pin "A") (pinfunction "A_A") (pintype "passive"))
      (node (ref "R5") (pin "1") (pinfunction "1_1") (pintype "passive"))
    )
    (net (code "49") (name "Net-(LED4-PadA)") (class "Default")
      (node (ref "LED4") (pin "A") (pinfunction "A_A") (pintype "passive"))
      (node (ref "R7") (pin "1") (pinfunction "1_1") (pintype "passive"))
    )
    (net (code "50") (name "Net-(LED5-PadA)") (class "Default")
      (node (ref "LED5") (pin "A") (pinfunction "A_A") (pintype "passive"))
      (node (ref "R21") (pin "1") (pinfunction "1_1") (pintype "passive"))
    )
    (net (code "51") (name "Net-(M2-VCC)") (class "Default")
      (node (ref "C20") (pin "1") (pinfunction "1_1") (pintype "passive"))
      (node (ref "C7") (pin "1") (pinfunction "1_1") (pintype "passive"))
      (node (ref "L4") (pin "2") (pinfunction "2_2") (pintype "passive"))
      (node (ref "M2") (pin "2") (pinfunction "VCC_2") (pintype "power_in"))
    )
    (net (code "52") (name "Net-(Q1-B)") (class "Default")
      (node (ref "Q1") (pin "1") (pinfunction "B_1") (pintype "passive"))
      (node (ref "R44") (pin "1") (pinfunction "1_1") (pintype "passive"))
    )
    (net (code "53") (name "Net-(Q2-B)") (class "Default")
      (node (ref "Q2") (pin "1") (pinfunction "B_1") (pintype "passive"))
      (node (ref "R43") (pin "1") (pinfunction "1_1") (pintype "passive"))
    )
    (net (code "54") (name "Net-(Q3-G)") (class "Default")
      (node (ref "Q3") (pin "1") (pinfunction "G_1") (pintype "bidirectional"))
      (node (ref "R25") (pin "1") (pinfunction "1_1") (pintype "passive"))
    )
    (net (code "55") (name "Net-(Q3-S)") (class "Default")
      (node (ref "Q3") (pin "2") (pinfunction "S_2") (pintype "bidirectional"))
      (node (ref "R26") (pin "1") (pinfunction "1_1") (pintype "passive"))
    )
    (net (code "56") (name "Net-(Q4-G)") (class "Default")
      (node (ref "Q4") (pin "1") (pinfunction "G_1") (pintype "bidirectional"))
      (node (ref "R28") (pin "1") (pinfunction "1_1") (pintype "passive"))
    )
    (net (code "57") (name "Net-(Q4-S)") (class "Default")
      (node (ref "Q4") (pin "2") (pinfunction "S_2") (pintype "bidirectional"))
      (node (ref "R31") (pin "1") (pinfunction "1_1") (pintype "passive"))
    )
    (net (code "58") (name "Net-(Q6-D)") (class "Default")
      (node (ref "BUZ1") (pin "-") (pinfunction "-_-") (pintype "passive"))
      (node (ref "Q6") (pin "3") (pinfunction "D_3") (pintype "bidirectional"))
    )
    (net (code "59") (name "Net-(Q6-G)") (class "Default")
      (node (ref "Q6") (pin "1") (pinfunction "G_1") (pintype "bidirectional"))
      (node (ref "R2") (pin "1") (pinfunction "1_1") (pintype "passive"))
      (node (ref "R3") (pin "2") (pinfunction "2_2") (pintype "passive"))
    )
    (net (code "60") (name "Net-(Q9-G)") (class "Default")
      (node (ref "Q9") (pin "1") (pinfunction "G_1") (pintype "bidirectional"))
      (node (ref "R33") (pin "1") (pinfunction "1_1") (pintype "passive"))
    )
    (net (code "61") (name "Net-(Q9-S)") (class "Default")
      (node (ref "Q9") (pin "2") (pinfunction "S_2") (pintype "bidirectional"))
      (node (ref "R34") (pin "1") (pinfunction "1_1") (pintype "passive"))
    )
    (net (code "62") (name "Net-(Q10-G)") (class "Default")
      (node (ref "Q10") (pin "1") (pinfunction "G_1") (pintype "bidirectional"))
      (node (ref "R36") (pin "1") (pinfunction "1_1") (pintype "passive"))
    )
    (net (code "63") (name "Net-(Q10-S)") (class "Default")
      (node (ref "Q10") (pin "2") (pinfunction "S_2") (pintype "bidirectional"))
      (node (ref "R37") (pin "1") (pinfunction "1_1") (pintype "passive"))
    )
    (net (code "64") (name "Net-(Q11-G)") (class "Default")
      (node (ref "Q11") (pin "1") (pinfunction "G_1") (pintype "bidirectional"))
      (node (ref "R39") (pin "1") (pinfunction "1_1") (pintype "passive"))
    )
    (net (code "65") (name "Net-(Q11-S)") (class "Default")
      (node (ref "Q11") (pin "2") (pinfunction "S_2") (pintype "bidirectional"))
      (node (ref "R40") (pin "1") (pinfunction "1_1") (pintype "passive"))
    )
    (net (code "66") (name "Net-(R19-Pad1)") (class "Default")
      (node (ref "R19") (pin "1") (pinfunction "1_1") (pintype "passive"))
      (node (ref "SJ4") (pin "2") (pinfunction "2_2") (pintype "passive"))
    )
    (net (code "67") (name "Net-(R20-Pad1)") (class "Default")
      (node (ref "R20") (pin "1") (pinfunction "1_1") (pintype "passive"))
      (node (ref "U$2") (pin "RST") (pinfunction "RST_RST") (pintype "bidirectional"))
    )
    (net (code "68") (name "Net-(R22-Pad1)") (class "Default")
      (node (ref "R22") (pin "1") (pinfunction "1_1") (pintype "passive"))
      (node (ref "U1") (pin "CH_PD") (pinfunction "CH_PD_CH_PD") (pintype "bidirectional"))
    )
    (net (code "69") (name "Net-(R27-Pad2)") (class "Default")
      (node (ref "R27") (pin "2") (pinfunction "2_2") (pintype "passive"))
      (node (ref "SJ5") (pin "1") (pinfunction "1_1") (pintype "passive"))
    )
    (net (code "70") (name "Net-(R42-Pad2)") (class "Default")
      (node (ref "R42") (pin "2") (pinfunction "2_2") (pintype "passive"))
      (node (ref "SJ1") (pin "2") (pinfunction "2_2") (pintype "passive"))
    )
    (net (code "71") (name "Net-(R45-Pad2)") (class "Default")
      (node (ref "R45") (pin "2") (pinfunction "2_2") (pintype "passive"))
      (node (ref "SJ3") (pin "2") (pinfunction "2_2") (pintype "passive"))
    )
    (net (code "72") (name "Net-(U$2-RXD)") (class "Default")
      (node (ref "R23") (pin "1") (pinfunction "1_1") (pintype "passive"))
      (node (ref "U$2") (pin "RX") (pinfunction "RXD_RX") (pintype "bidirectional"))
    )
    (net (code "73") (name "Net-(U$2-TXD)") (class "Default")
      (node (ref "R24") (pin "1") (pinfunction "1_1") (pintype "passive"))
      (node (ref "U$2") (pin "TX") (pinfunction "TXD_TX") (pintype "bidirectional"))
    )
    (net (code "74") (name "Net-(U3-VBAT)") (class "Default")
      (node (ref "BAT1") (pin "+") (pinfunction "+_+") (pintype "bidirectional"))
      (node (ref "U3") (pin "3") (pinfunction "VBAT_3") (pintype "bidirectional"))
    )
    (net (code "75") (name "Net-(U3-X1)") (class "Default")
      (node (ref "Q8") (pin "2") (pinfunction "2_2") (pintype "passive"))
      (node (ref "U3") (pin "1") (pinfunction "X1_1") (pintype "bidirectional"))
      (node (ref "X1") (pin "P$2") (pinfunction "P$2_P$2") (pintype "bidirectional"))
    )
    (net (code "76") (name "Net-(U3-X2)") (class "Default")
      (node (ref "Q8") (pin "1") (pinfunction "1_1") (pintype "passive"))
      (node (ref "U3") (pin "2") (pinfunction "X2_2") (pintype "bidirectional"))
      (node (ref "X1") (pin "P$1") (pinfunction "P$1_P$1") (pintype "bidirectional"))
    )
    (net (code "77") (name "Net-(U6-PB6(XTAL1{slash}TOSC1))") (class "Default")
      (node (ref "C22") (pin "1") (pinfunction "1_1") (pintype "passive"))
      (node (ref "Q14") (pin "2") (pinfunction "2_2") (pintype "passive"))
      (node (ref "U6") (pin "7") (pinfunction "PB6(XTAL1/TOSC1)_7") (pintype "bidirectional"))
    )
    (net (code "78") (name "Net-(U6-PB7(XTAL2{slash}TOSC2))") (class "Default")
      (node (ref "C23") (pin "1") (pinfunction "1_1") (pintype "passive"))
      (node (ref "Q14") (pin "1") (pinfunction "1_1") (pintype "passive"))
      (node (ref "U6") (pin "8") (pinfunction "PB7(XTAL2/TOSC2)_8") (pintype "bidirectional"))
    )
    (net (code "79") (name "PIPE_RX") (class "Default")
      (node (ref "U1") (pin "GPIO13") (pinfunction "GPIO13_GPIO13") (pintype "bidirectional"))
      (node (ref "U6") (pin "1") (pinfunction "PD3(INT1)_1") (pintype "bidirectional"))
    )
    (net (code "80") (name "PIPE_TX") (class "Default")
      (node (ref "U1") (pin "GPIO12") (pinfunction "GPIO12_GPIO12") (pintype "bidirectional"))
      (node (ref "U6") (pin "2") (pinfunction "PD4(XCK/T0)_2") (pintype "bidirectional"))
    )
    (net (code "81") (name "RESET") (class "Default")
      (node (ref "C31") (pin "1") (pinfunction "1_1") (pintype "passive"))
      (node (ref "JP8") (pin "5") (pinfunction "5_5") (pintype "passive"))
      (node (ref "R49") (pin "1") (pinfunction "1_1") (pintype "passive"))
      (node (ref "SJ6") (pin "1") (pinfunction "1_1") (pintype "passive"))
      (node (ref "U6") (pin "29") (pinfunction "PC6(/RESET)_29") (pintype "bidirectional"))
    )
    (net (code "82") (name "RF_IRQ") (class "Default")
      (node (ref "M2") (pin "8") (pinfunction "IRQ_8") (pintype "bidirectional"))
    )
    (net (code "83") (name "RXD") (class "Default")
      (node (ref "JP6") (pin "2") (pinfunction "2_2") (pintype "passive"))
      (node (ref "U6") (pin "30") (pinfunction "PD0(RXD)_30") (pintype "bidirectional"))
    )
    (net (code "84") (name "SCK") (class "Default")
      (node (ref "JP8") (pin "7") (pinfunction "7_7") (pintype "passive"))
      (node (ref "R40") (pin "2") (pinfunction "2_2") (pintype "passive"))
      (node (ref "U6") (pin "17") (pinfunction "PB5(SCK)_17") (pintype "bidirectional"))
    )
    (net (code "85") (name "SCK_3V3") (class "Default")
      (node (ref "IC3") (pin "6") (pinfunction "CLK_6") (pintype "bidirectional"))
      (node (ref "M2") (pin "5") (pinfunction "SCK_5") (pintype "bidirectional"))
      (node (ref "Q11") (pin "3") (pinfunction "D_3") (pintype "bidirectional"))
      (node (ref "R38") (pin "1") (pinfunction "1_1") (pintype "passive"))
    )
    (net (code "86") (name "SCL") (class "Default")
      (node (ref "R29") (pin "1") (pinfunction "1_1") (pintype "passive"))
      (node (ref "U3") (pin "6") (pinfunction "SCL_6") (pintype "bidirectional"))
      (node (ref "U6") (pin "28") (pinfunction "PC5(ADC5/SCL)_28") (pintype "bidirectional"))
    )
    (net (code "87") (name "SDA") (class "Default")
      (node (ref "R30") (pin "1") (pinfunction "1_1") (pintype "passive"))
      (node (ref "U3") (pin "5") (pinfunction "SDA_5") (pintype "bidirectional"))
      (node (ref "U6") (pin "27") (pinfunction "PC4(ADC4/SDA)_27") (pintype "bidirectional"))
    )
    (net (code "88") (name "SERVER_LED") (class "Default")
      (node (ref "R1") (pin "2") (pinfunction "2_2") (pintype "passive"))
      (node (ref "U1") (pin "GPIO16") (pinfunction "GPIO16_GPIO16") (pintype "bidirectional"))
    )
    (net (code "89") (name "TXD") (class "Default")
      (node (ref "JP6") (pin "1") (pinfunction "1_1") (pintype "passive"))
      (node (ref "U6") (pin "31") (pinfunction "PD1(TXD)_31") (pintype "bidirectional"))
    )
    (net (code "90") (name "VCC") (class "Default")
      (node (ref "BUZ1") (pin "+") (pinfunction "+_+") (pintype "passive"))
      (node (ref "C10") (pin "1") (pinfunction "1_1") (pintype "passive"))
      (node (ref "C12") (pin "1") (pinfunction "1_1") (pintype "passive"))
      (node (ref "C17") (pin "+") (pinfunction "+_+") (pintype "passive"))
      (node (ref "C19") (pin "1") (pinfunction "1_1") (pintype "passive"))
      (node (ref "C27") (pin "1") (pinfunction "+_1") (pintype "passive"))
      (node (ref "C3") (pin "1") (pinfunction "1_1") (pintype "passive"))
      (node (ref "C5") (pin "1") (pinfunction "1_1") (pintype "passive"))
      (node (ref "C8") (pin "+") (pinfunction "+_+") (pintype "passive"))
      (node (ref "JP6") (pin "4") (pinfunction "4_4") (pintype "passive"))
      (node (ref "JP7") (pin "1") (pinfunction "1_1") (pintype "passive"))
      (node (ref "JP8") (pin "2") (pinfunction "2_2") (pintype "passive"))
      (node (ref "L3") (pin "1") (pinfunction "1_1") (pintype "passive"))
      (node (ref "R14") (pin "1") (pinfunction "1_1") (pintype "passive"))
      (node (ref "R18") (pin "2") (pinfunction "2_2") (pintype "passive"))
      (node (ref "R21") (pin "2") (pinfunction "2_2") (pintype "passive"))
      (node (ref "R25") (pin "2") (pinfunction "2_2") (pintype "passive"))
      (node (ref "R28") (pin "2") (pinfunction "2_2") (pintype "passive"))
      (node (ref "R29") (pin "2") (pinfunction "2_2") (pintype "passive"))
      (node (ref "R30") (pin "2") (pinfunction "2_2") (pintype "passive"))
      (node (ref "R33") (pin "2") (pinfunction "2_2") (pintype "passive"))
      (node (ref "R36") (pin "2") (pinfunction "2_2") (pintype "passive"))
      (node (ref "R39") (pin "2") (pinfunction "2_2") (pintype "passive"))
      (node (ref "R49") (pin "2") (pinfunction "2_2") (pintype "passive"))
      (node (ref "SJ2") (pin "2") (pinfunction "2_2") (pintype "passive"))
      (node (ref "SJ7") (pin "1") (pinfunction "1_1") (pintype "passive"))
      (node (ref "U3") (pin "8") (pinfunction "VCC_8") (pintype "bidirectional"))
      (node (ref "U6") (pin "18") (pinfunction "AVCC_18") (pintype "bidirectional"))
      (node (ref "U6") (pin "4") (pinfunction "VCC_4") (pintype "bidirectional"))
      (node (ref "U6") (pin "6") (pinfunction "VCC_6") (pintype "bidirectional"))
      (node (ref "VR1") (pin "3") (pinfunction "IN_3") (pintype "input"))
    )
    (net (code "91") (name "WIFI_LED") (class "Default")
      (node (ref "R4") (pin "2") (pinfunction "2_2") (pintype "passive"))
      (node (ref "U1") (pin "ADC") (pinfunction "ADC_ADC") (pintype "bidirectional"))
    )
    (net (code "92") (name "unconnected-(JP8-Pad3)") (class "Default")
      (node (ref "JP8") (pin "3") (pinfunction "3_3") (pintype "passive"))
    )
    (net (code "93") (name "unconnected-(U$2-+MIC-PadMIC+)") (class "Default")
      (node (ref "U$2") (pin "MIC+") (pinfunction "+MIC_MIC+") (pintype "bidirectional"))
    )
    (net (code "94") (name "unconnected-(U$2-+SPK-PadSPK+)") (class "Default")
      (node (ref "U$2") (pin "SPK+") (pinfunction "+SPK_SPK+") (pintype "bidirectional"))
    )
    (net (code "95") (name "unconnected-(U$2--MIC-PadMIC-)") (class "Default")
      (node (ref "U$2") (pin "MIC-") (pinfunction "-MIC_MIC-") (pintype "bidirectional"))
    )
    (net (code "96") (name "unconnected-(U$2--SPK-PadSPK-)") (class "Default")
      (node (ref "U$2") (pin "SPK-") (pinfunction "-SPK_SPK-") (pintype "bidirectional"))
    )
    (net (code "97") (name "unconnected-(U$2-PadDTR)") (class "Default")
      (node (ref "U$2") (pin "DTR") (pinfunction "DTR_DTR") (pintype "bidirectional"))
    )
    (net (code "98") (name "unconnected-(U$2-PadNET)") (class "Default")
      (node (ref "U$2") (pin "NET") (pinfunction "NET_NET") (pintype "bidirectional"))
    )
    (net (code "99") (name "unconnected-(U$2-PadRING)") (class "Default")
      (node (ref "U$2") (pin "RING") (pinfunction "RING_RING") (pintype "bidirectional"))
    )
    (net (code "100") (name "unconnected-(U1-*GPIO9-PadGPIO9)") (class "Default")
      (node (ref "U1") (pin "GPIO9") (pinfunction "*GPIO9_GPIO9") (pintype "bidirectional"))
    )
    (net (code "101") (name "unconnected-(U1-*GPIO10-PadGPIO10)") (class "Default")
      (node (ref "U1") (pin "GPIO10") (pinfunction "*GPIO10_GPIO10") (pintype "bidirectional"))
    )
    (net (code "102") (name "unconnected-(U1-PadCS0)") (class "Default")
      (node (ref "U1") (pin "CS0") (pinfunction "CS0_CS0") (pintype "bidirectional"))
    )
    (net (code "103") (name "unconnected-(U1-PadMISO)") (class "Default")
      (node (ref "U1") (pin "MISO") (pinfunction "MISO_MISO") (pintype "bidirectional"))
    )
    (net (code "104") (name "unconnected-(U1-PadMOSI)") (class "Default")
      (node (ref "U1") (pin "MOSI") (pinfunction "MOSI_MOSI") (pintype "bidirectional"))
    )
    (net (code "105") (name "unconnected-(U1-PadSCLK)") (class "Default")
      (node (ref "U1") (pin "SCLK") (pinfunction "SCLK_SCLK") (pintype "bidirectional"))
    )
    (net (code "106") (name "unconnected-(U3-SQW{slash}OUT-Pad7)") (class "Default")
      (node (ref "U3") (pin "7") (pinfunction "SQW/OUT_7") (pintype "bidirectional"))
    )
  )
)
